# 1_RPi.net
KiCad netlist of a schematic drawn in Altium Designer
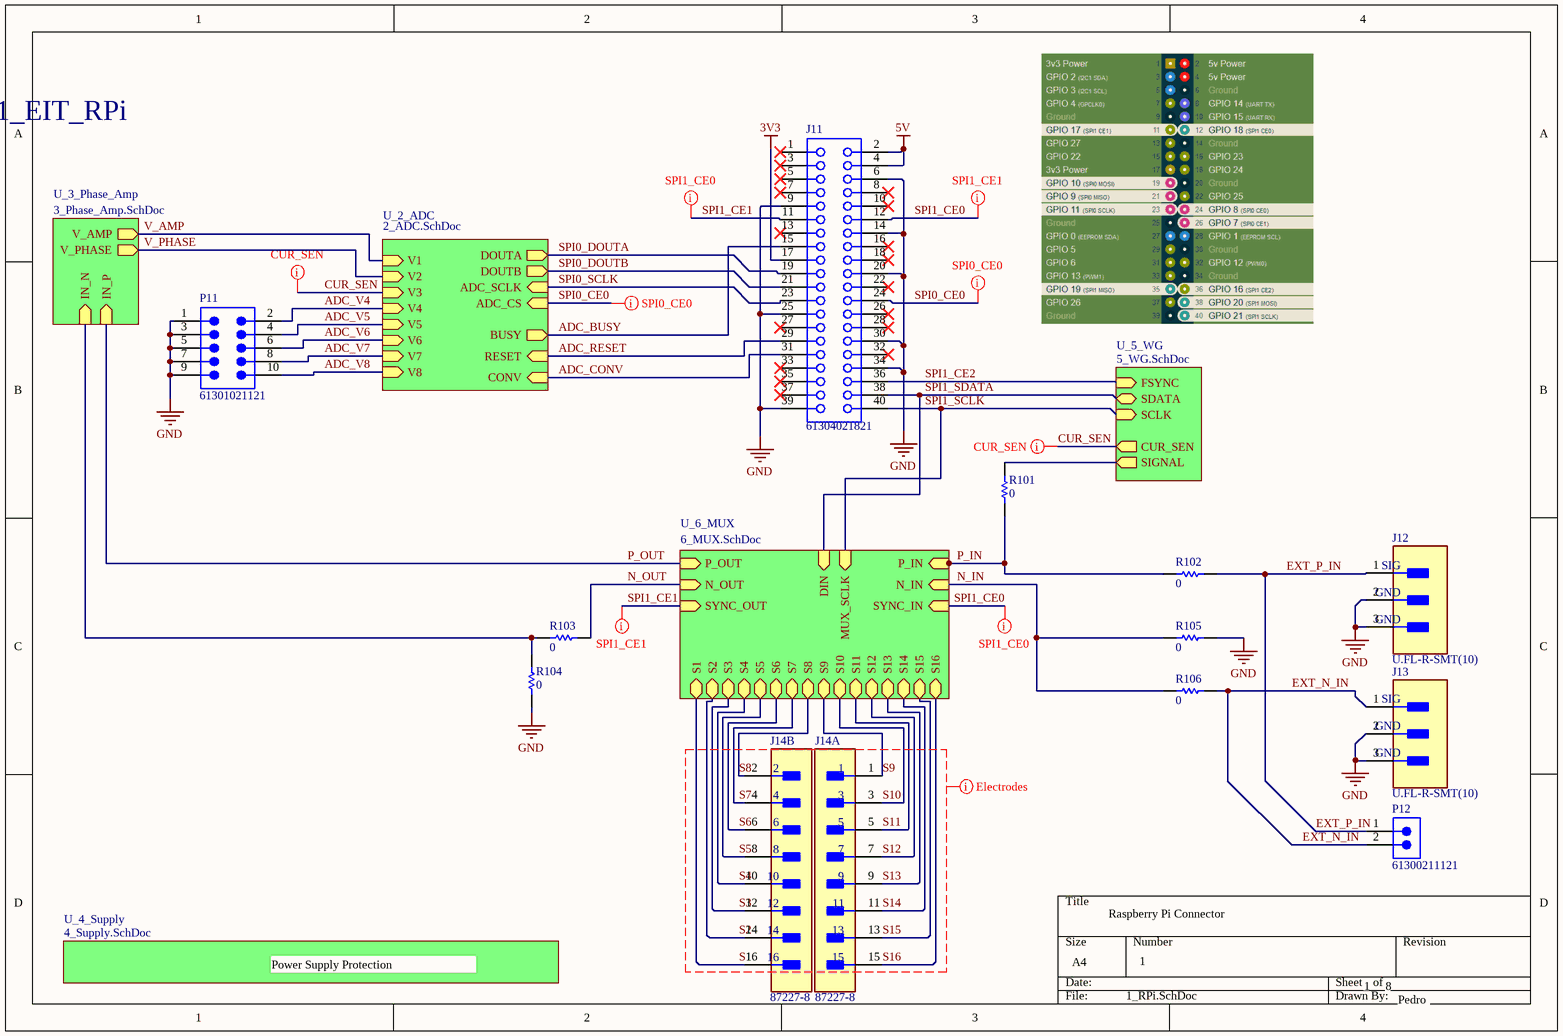
[diagram p0: 1_RPi.SchDoc]

(export (version "E")
  (design (tool "Eeschema 10.0.6"))
  (components
    (comp (ref "J11")
      (value "61304021821")
      (footprint "61304021821")
      (libsource (lib "Altium Content Vault") (part "Header_Female_2R_40P"))
    )
    (comp (ref "J12")
      (value "U.FL-R-SMT(10)")
      (footprint "FP-U_FL-R-SMT_10-MFG")
      (description "CONN U.FL RCPT STR 50 OHM SMD")
      (libsource (lib "RPI_EIT_SchLib") (part "eef6fde44c591823e8076210edfe12f"))
    )
    (comp (ref "J13")
      (value "U.FL-R-SMT(10)")
      (footprint "FP-U_FL-R-SMT_10-MFG")
      (description "CONN U.FL RCPT STR 50 OHM SMD")
      (libsource (lib "RPI_EIT_SchLib") (part "eef6fde44c591823e8076210edfe12f"))
    )
    (comp (ref "J14")
      (value "87227-8")
      (footprint "FP-87227-8-MFG")
      (description "CONN HEADER VERT 16POS 2.54MM")
      (fields
        (field (name "MANUFACTURER") "TE Connectivity")
        (field (name "OCTOPART") "https://octopart.com/87227-8-te+connectivity-39407754")
      )
      (libsource (lib "Altium Content Vault") (part "4b6d22b45e2f925f038cba5d936fbcc"))
    )
    (comp (ref "P11")
      (value "61301021121")
      (footprint "61301021121")
      (libsource (lib "RPI_EIT_SchLib") (part "Header_Male_2R_10P"))
    )
    (comp (ref "P12")
      (value "61300211121")
      (footprint "61300211121")
      (libsource (lib "Altium Content Vault") (part "Header_Male_1R_02P"))
    )
    (comp (ref "R101")
      (value "RC0603JR-070RL")
      (footprint "RESC1608X55X25LL10T15")
      (description "Chip Resistor, 0 Ohm, +/- 5%, 0.1 W, -55 to 155 degC, 0603 (1608 Metric), RoHS, Tape and Reel")
      (fields
        (field (name "TOLERANCE") "5%")
        (field (name "RESISTANCE") "0")
        (field (name "MANUFACTURER") "Yageo")
      )
      (libsource (lib "RPI_EIT_SchLib") (part "RES-2"))
    )
    (comp (ref "R102")
      (value "RC0603JR-070RL")
      (footprint "RESC1608X55X25LL10T15")
      (description "Chip Resistor, 0 Ohm, +/- 5%, 0.1 W, -55 to 155 degC, 0603 (1608 Metric), RoHS, Tape and Reel")
      (fields
        (field (name "TOLERANCE") "5%")
        (field (name "RESISTANCE") "0")
        (field (name "MANUFACTURER") "Yageo")
      )
      (libsource (lib "RPI_EIT_SchLib") (part "RES-2"))
    )
    (comp (ref "R103")
      (value "RC0603JR-070RL")
      (footprint "RESC1608X55X25LL10T15")
      (description "Chip Resistor, 0 Ohm, +/- 5%, 0.1 W, -55 to 155 degC, 0603 (1608 Metric), RoHS, Tape and Reel")
      (fields
        (field (name "TOLERANCE") "5%")
        (field (name "RESISTANCE") "0")
        (field (name "MANUFACTURER") "Yageo")
      )
      (libsource (lib "RPI_EIT_SchLib") (part "RES-2"))
    )
    (comp (ref "R104")
      (value "RC0603JR-070RL")
      (footprint "RESC1608X55X25LL10T15")
      (description "Chip Resistor, 0 Ohm, +/- 5%, 0.1 W, -55 to 155 degC, 0603 (1608 Metric), RoHS, Tape and Reel")
      (fields
        (field (name "TOLERANCE") "5%")
        (field (name "RESISTANCE") "0")
        (field (name "MANUFACTURER") "Yageo")
      )
      (libsource (lib "RPI_EIT_SchLib") (part "RES-2"))
    )
    (comp (ref "R105")
      (value "RC0603JR-070RL")
      (footprint "RESC1608X55X25LL10T15")
      (description "Chip Resistor, 0 Ohm, +/- 5%, 0.1 W, -55 to 155 degC, 0603 (1608 Metric), RoHS, Tape and Reel")
      (fields
        (field (name "TOLERANCE") "5%")
        (field (name "RESISTANCE") "0")
        (field (name "MANUFACTURER") "Yageo")
      )
      (libsource (lib "RPI_EIT_SchLib") (part "RES-2"))
    )
    (comp (ref "R106")
      (value "RC0603JR-070RL")
      (footprint "RESC1608X55X25LL10T15")
      (description "Chip Resistor, 0 Ohm, +/- 5%, 0.1 W, -55 to 155 degC, 0603 (1608 Metric), RoHS, Tape and Reel")
      (fields
        (field (name "TOLERANCE") "5%")
        (field (name "RESISTANCE") "0")
        (field (name "MANUFACTURER") "Yageo")
      )
      (libsource (lib "RPI_EIT_SchLib") (part "RES-2"))
    )
  )
  (nets
    (net (code "1") (name "/ADC_BUSY") (class "Default")
      (node (ref "J11") (pin "15") (pinfunction "15_15") (pintype "passive"))
    )
    (net (code "2") (name "/ADC_CONV") (class "Default")
      (node (ref "J11") (pin "31") (pinfunction "31_31") (pintype "passive"))
    )
    (net (code "3") (name "/ADC_RESET") (class "Default")
      (node (ref "J11") (pin "29") (pinfunction "29_29") (pintype "passive"))
    )
    (net (code "4") (name "/ADC_V4") (class "Default")
      (node (ref "P11") (pin "2") (pinfunction "2_2") (pintype "passive"))
    )
    (net (code "5") (name "/ADC_V5") (class "Default")
      (node (ref "P11") (pin "4") (pinfunction "4_4") (pintype "passive"))
    )
    (net (code "6") (name "/ADC_V6") (class "Default")
      (node (ref "P11") (pin "6") (pinfunction "6_6") (pintype "passive"))
    )
    (net (code "7") (name "/ADC_V7") (class "Default")
      (node (ref "P11") (pin "8") (pinfunction "8_8") (pintype "passive"))
    )
    (net (code "8") (name "/ADC_V8") (class "Default")
      (node (ref "P11") (pin "10") (pinfunction "10_10") (pintype "passive"))
    )
    (net (code "10") (name "/EXT_N_IN") (class "Default")
      (node (ref "J13") (pin "1") (pinfunction "SIG_1") (pintype "passive"))
      (node (ref "P12") (pin "2") (pinfunction "2_2") (pintype "passive"))
      (node (ref "R106") (pin "1") (pinfunction "1_1") (pintype "passive"))
    )
    (net (code "11") (name "/EXT_P_IN") (class "Default")
      (node (ref "J12") (pin "1") (pinfunction "SIG_1") (pintype "passive"))
      (node (ref "P12") (pin "1") (pinfunction "1_1") (pintype "passive"))
      (node (ref "R102") (pin "1") (pinfunction "1_1") (pintype "passive"))
    )
    (net (code "12") (name "/IN_N") (class "Default")
      (node (ref "R103") (pin "2") (pinfunction "2_2") (pintype "passive"))
      (node (ref "R104") (pin "1") (pinfunction "1_1") (pintype "passive"))
    )
    (net (code "13") (name "/N_IN") (class "Default")
      (node (ref "R105") (pin "2") (pinfunction "2_2") (pintype "passive"))
      (node (ref "R106") (pin "2") (pinfunction "2_2") (pintype "passive"))
    )
    (net (code "14") (name "/N_OUT") (class "Default")
      (node (ref "R103") (pin "1") (pinfunction "1_1") (pintype "passive"))
    )
    (net (code "15") (name "/P_IN") (class "Default")
      (node (ref "R101") (pin "2") (pinfunction "2_2") (pintype "passive"))
      (node (ref "R102") (pin "2") (pinfunction "2_2") (pintype "passive"))
    )
    (net (code "17") (name "/S1") (class "Default")
      (node (ref "J14") (pin "16") (pinfunction "16_16") (pintype "passive"))
    )
    (net (code "18") (name "/S2") (class "Default")
      (node (ref "J14") (pin "14") (pinfunction "14_14") (pintype "passive"))
    )
    (net (code "19") (name "/S3") (class "Default")
      (node (ref "J14") (pin "12") (pinfunction "12_12") (pintype "passive"))
    )
    (net (code "20") (name "/S4") (class "Default")
      (node (ref "J14") (pin "10") (pinfunction "10_10") (pintype "passive"))
    )
    (net (code "21") (name "/S5") (class "Default")
      (node (ref "J14") (pin "8") (pinfunction "8_8") (pintype "passive"))
    )
    (net (code "22") (name "/S6") (class "Default")
      (node (ref "J14") (pin "6") (pinfunction "6_6") (pintype "passive"))
    )
    (net (code "23") (name "/S7") (class "Default")
      (node (ref "J14") (pin "4") (pinfunction "4_4") (pintype "passive"))
    )
    (net (code "24") (name "/S8") (class "Default")
      (node (ref "J14") (pin "2") (pinfunction "2_2") (pintype "passive"))
    )
    (net (code "25") (name "/S9") (class "Default")
      (node (ref "J14") (pin "1") (pinfunction "1_1") (pintype "passive"))
    )
    (net (code "26") (name "/S10") (class "Default")
      (node (ref "J14") (pin "3") (pinfunction "3_3") (pintype "passive"))
    )
    (net (code "27") (name "/S11") (class "Default")
      (node (ref "J14") (pin "5") (pinfunction "5_5") (pintype "passive"))
    )
    (net (code "28") (name "/S12") (class "Default")
      (node (ref "J14") (pin "7") (pinfunction "7_7") (pintype "passive"))
    )
    (net (code "29") (name "/S13") (class "Default")
      (node (ref "J14") (pin "9") (pinfunction "9_9") (pintype "passive"))
    )
    (net (code "30") (name "/S14") (class "Default")
      (node (ref "J14") (pin "11") (pinfunction "11_11") (pintype "passive"))
    )
    (net (code "31") (name "/S15") (class "Default")
      (node (ref "J14") (pin "13") (pinfunction "13_13") (pintype "passive"))
    )
    (net (code "32") (name "/S16") (class "Default")
      (node (ref "J14") (pin "15") (pinfunction "15_15") (pintype "passive"))
    )
    (net (code "33") (name "/SIGNAL") (class "Default")
      (node (ref "R101") (pin "1") (pinfunction "1_1") (pintype "passive"))
    )
    (net (code "34") (name "/SPI0_CE0") (class "Default")
      (node (ref "J11") (pin "24") (pinfunction "24_24") (pintype "passive"))
    )
    (net (code "35") (name "/SPI0_DOUTA") (class "Default")
      (node (ref "J11") (pin "19") (pinfunction "19_19") (pintype "passive"))
    )
    (net (code "36") (name "/SPI0_DOUTB") (class "Default")
      (node (ref "J11") (pin "21") (pinfunction "21_21") (pintype "passive"))
    )
    (net (code "37") (name "/SPI0_SCLK") (class "Default")
      (node (ref "J11") (pin "23") (pinfunction "23_23") (pintype "passive"))
    )
    (net (code "38") (name "/SPI1_CE0") (class "Default")
      (node (ref "J11") (pin "12") (pinfunction "12_12") (pintype "passive"))
    )
    (net (code "39") (name "/SPI1_CE1") (class "Default")
      (node (ref "J11") (pin "11") (pinfunction "11_11") (pintype "passive"))
    )
    (net (code "40") (name "/SPI1_CE2") (class "Default")
      (node (ref "J11") (pin "36") (pinfunction "36_36") (pintype "passive"))
    )
    (net (code "41") (name "/SPI1_SCLK") (class "Default")
      (node (ref "J11") (pin "40") (pinfunction "40_40") (pintype "passive"))
    )
    (net (code "42") (name "/SPI1_SDATA") (class "Default")
      (node (ref "J11") (pin "38") (pinfunction "38_38") (pintype "passive"))
    )
    (net (code "45") (name "3V3") (class "Default")
      (node (ref "J11") (pin "17") (pinfunction "17_17") (pintype "passive"))
    )
    (net (code "46") (name "5V") (class "Default")
      (node (ref "J11") (pin "2") (pinfunction "2_2") (pintype "passive"))
      (node (ref "J11") (pin "4") (pinfunction "4_4") (pintype "passive"))
    )
    (net (code "47") (name "GND") (class "Default")
      (node (ref "J11") (pin "14") (pinfunction "14_14") (pintype "passive"))
      (node (ref "J11") (pin "20") (pinfunction "20_20") (pintype "passive"))
      (node (ref "J11") (pin "25") (pinfunction "25_25") (pintype "passive"))
      (node (ref "J11") (pin "30") (pinfunction "30_30") (pintype "passive"))
      (node (ref "J11") (pin "34") (pinfunction "34_34") (pintype "passive"))
      (node (ref "J11") (pin "39") (pinfunction "39_39") (pintype "passive"))
      (node (ref "J11") (pin "6") (pinfunction "6_6") (pintype "passive"))
      (node (ref "J11") (pin "9") (pinfunction "9_9") (pintype "passive"))
      (node (ref "J12") (pin "2") (pinfunction "GND_2") (pintype "power_in"))
      (node (ref "J12") (pin "3") (pinfunction "GND_3") (pintype "power_in"))
      (node (ref "J13") (pin "2") (pinfunction "GND_2") (pintype "power_in"))
      (node (ref "J13") (pin "3") (pinfunction "GND_3") (pintype "power_in"))
      (node (ref "P11") (pin "1") (pinfunction "1_1") (pintype "passive"))
      (node (ref "P11") (pin "3") (pinfunction "3_3") (pintype "passive"))
      (node (ref "P11") (pin "5") (pinfunction "5_5") (pintype "passive"))
      (node (ref "P11") (pin "7") (pinfunction "7_7") (pintype "passive"))
      (node (ref "P11") (pin "9") (pinfunction "9_9") (pintype "passive"))
      (node (ref "R104") (pin "2") (pinfunction "2_2") (pintype "passive"))
      (node (ref "R105") (pin "1") (pinfunction "1_1") (pintype "passive"))
    )
    (net (code "48") (name "unconnected-(J11-Pad1)") (class "Default")
      (node (ref "J11") (pin "1") (pinfunction "1_1") (pintype "passive+no_connect"))
    )
    (net (code "49") (name "unconnected-(J11-Pad3)") (class "Default")
      (node (ref "J11") (pin "3") (pinfunction "3_3") (pintype "passive+no_connect"))
    )
    (net (code "50") (name "unconnected-(J11-Pad5)") (class "Default")
      (node (ref "J11") (pin "5") (pinfunction "5_5") (pintype "passive+no_connect"))
    )
    (net (code "51") (name "unconnected-(J11-Pad7)") (class "Default")
      (node (ref "J11") (pin "7") (pinfunction "7_7") (pintype "passive+no_connect"))
    )
    (net (code "52") (name "unconnected-(J11-Pad8)") (class "Default")
      (node (ref "J11") (pin "8") (pinfunction "8_8") (pintype "passive+no_connect"))
    )
    (net (code "53") (name "unconnected-(J11-Pad10)") (class "Default")
      (node (ref "J11") (pin "10") (pinfunction "10_10") (pintype "passive+no_connect"))
    )
    (net (code "54") (name "unconnected-(J11-Pad13)") (class "Default")
      (node (ref "J11") (pin "13") (pinfunction "13_13") (pintype "passive+no_connect"))
    )
    (net (code "55") (name "unconnected-(J11-Pad16)") (class "Default")
      (node (ref "J11") (pin "16") (pinfunction "16_16") (pintype "passive+no_connect"))
    )
    (net (code "56") (name "unconnected-(J11-Pad18)") (class "Default")
      (node (ref "J11") (pin "18") (pinfunction "18_18") (pintype "passive+no_connect"))
    )
    (net (code "57") (name "unconnected-(J11-Pad22)") (class "Default")
      (node (ref "J11") (pin "22") (pinfunction "22_22") (pintype "passive+no_connect"))
    )
    (net (code "58") (name "unconnected-(J11-Pad26)") (class "Default")
      (node (ref "J11") (pin "26") (pinfunction "26_26") (pintype "passive+no_connect"))
    )
    (net (code "59") (name "unconnected-(J11-Pad27)") (class "Default")
      (node (ref "J11") (pin "27") (pinfunction "27_27") (pintype "passive+no_connect"))
    )
    (net (code "60") (name "unconnected-(J11-Pad28)") (class "Default")
      (node (ref "J11") (pin "28") (pinfunction "28_28") (pintype "passive+no_connect"))
    )
    (net (code "61") (name "unconnected-(J11-Pad32)") (class "Default")
      (node (ref "J11") (pin "32") (pinfunction "32_32") (pintype "passive+no_connect"))
    )
    (net (code "62") (name "unconnected-(J11-Pad33)") (class "Default")
      (node (ref "J11") (pin "33") (pinfunction "33_33") (pintype "passive+no_connect"))
    )
    (net (code "63") (name "unconnected-(J11-Pad35)") (class "Default")
      (node (ref "J11") (pin "35") (pinfunction "35_35") (pintype "passive+no_connect"))
    )
    (net (code "64") (name "unconnected-(J11-Pad37)") (class "Default")
      (node (ref "J11") (pin "37") (pinfunction "37_37") (pintype "passive+no_connect"))
    )
  )
)
